# MCU.net
KiCad netlist of a schematic drawn in Altium Designer
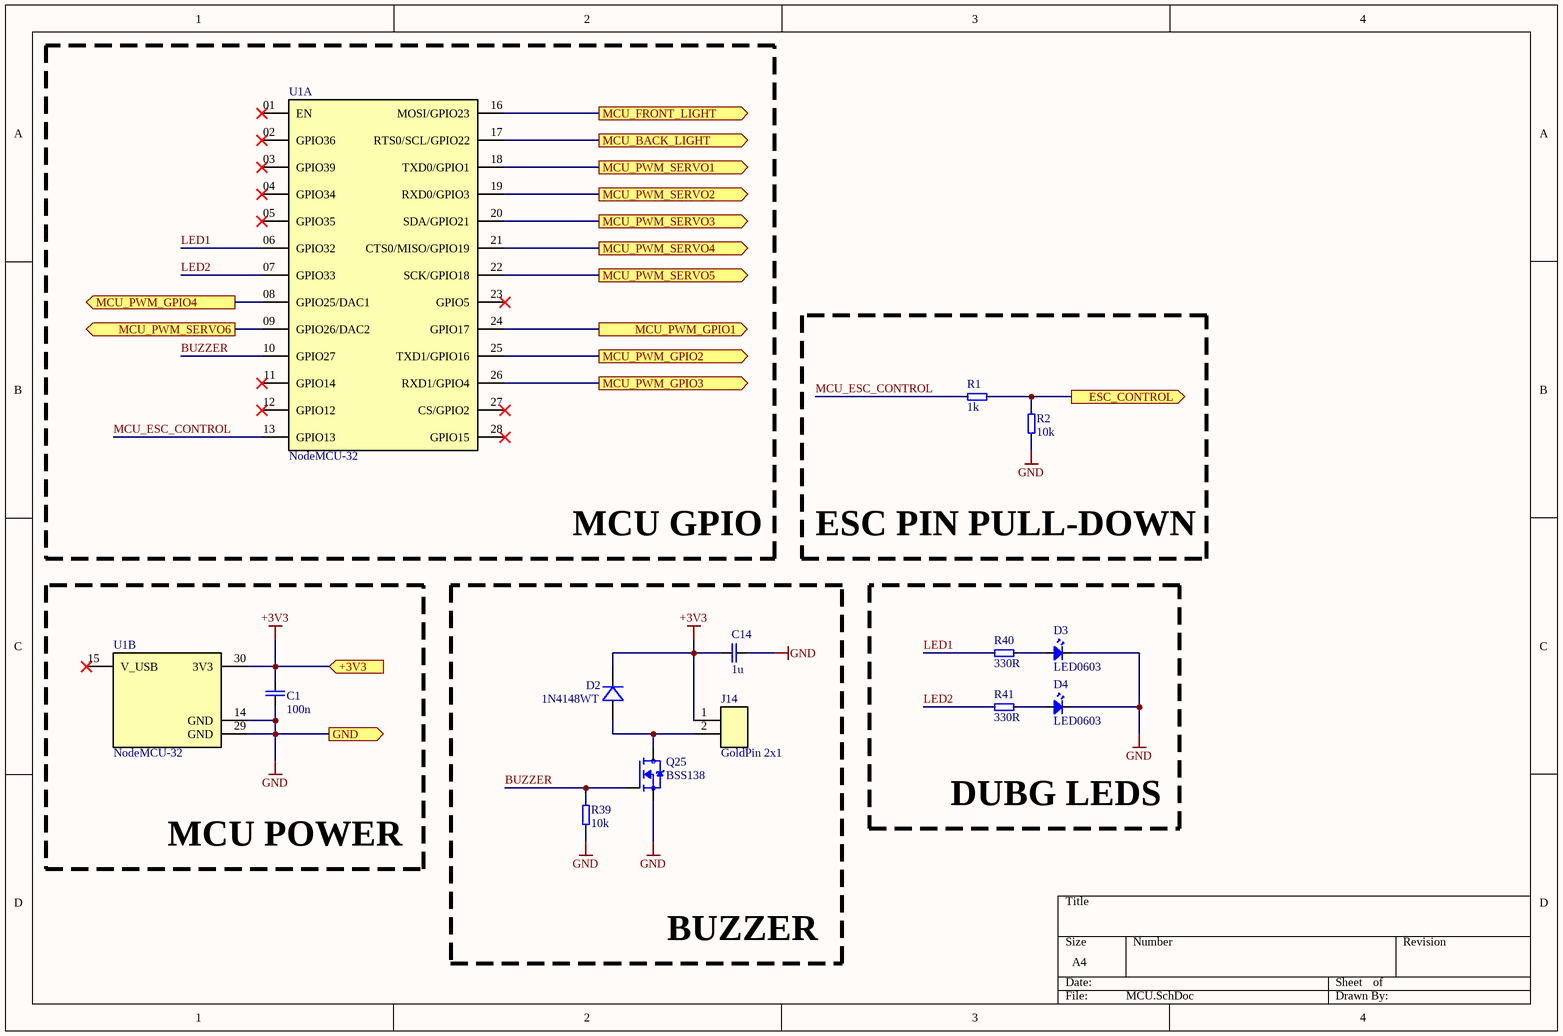
[diagram p0: MCU.SchDoc]

(export (version "E")
  (design (tool "Eeschema 10.0.6"))
  (components
    (comp (ref "C1")
      (value "100n")
      (footprint "C0402")
      (description "Generic SMD 0402 Ceramic Capacitor")
      (libsource (lib "PolSl Racing - Electrical") (part "Capacitor"))
    )
    (comp (ref "C14")
      (value "1u")
      (footprint "C0603")
      (description "Generic 0603 SMD Ceramic Capacitor")
      (libsource (lib "PolSl Racing - Electrical") (part "Capacitor"))
    )
    (comp (ref "D2")
      (value "1N4148WT")
      (footprint "SMBJSeries_LTF")
      (description "Description")
      (fields
        (field (name "MANUFACTURER_PART_NUMBER") "SMBJ7.0A")
        (field (name "COPYRIGHT") "Copyright (C) 2025 Ultra Librarian. All rights reserved.")
      )
      (libsource (lib "Tractor2000") (part "1N4148WT"))
    )
    (comp (ref "D3")
      (value "LED0603")
      (footprint "LED0603")
      (description "0603 LED")
      (libsource (lib "PolSl Racing - Electrical") (part "LED"))
    )
    (comp (ref "D4")
      (value "LED0603")
      (footprint "LED0603")
      (description "0603 LED")
      (libsource (lib "PolSl Racing - Electrical") (part "LED"))
    )
    (comp (ref "J14")
      (value "GoldPin 2x1")
      (footprint "HARWIN_M20-9990246")
      (description "2.54mm (0.1) Pitch SIL Vertical Throughboard Pin Header, 6.1mm mating pin height, tin, 2 contacts")
      (fields (field (name "MF") "Harwin") (field (name "MP") "M20-9990246"))
      (libsource (lib "Tractor2000") (part "GoldPin 2x1"))
    )
    (comp (ref "Q25")
      (value "BSS138")
      (footprint "SOT95P240X111-3N")
      (description "N-Channel 50 V 220mA (Ta) 350mW (Ta) Surface Mount SOT-23-3")
      (fields (field (name "MF") "onsemi"))
      (libsource (lib "Tractor2000") (part "BSS138"))
    )
    (comp (ref "R1")
      (value "1k")
      (footprint "R0402")
      (description "Generic 0402 SMD Resistor")
      (libsource (lib "PolSl Racing - Electrical") (part "Resistor"))
    )
    (comp (ref "R2")
      (value "10k")
      (footprint "R0402")
      (description "Generic 0402 SMD Resistor")
      (libsource (lib "PolSl Racing - Electrical") (part "Resistor"))
    )
    (comp (ref "R39")
      (value "10k")
      (footprint "R0603")
      (description "Generic 0603 SMD Resistor")
      (libsource (lib "PolSl Racing - Electrical") (part "Resistor"))
    )
    (comp (ref "R40")
      (value "330R")
      (footprint "R0603")
      (description "Generic 0603 SMD Resistor")
      (libsource (lib "PolSl Racing - Electrical") (part "Resistor"))
    )
    (comp (ref "R41")
      (value "330R")
      (footprint "R0603")
      (description "Generic 0603 SMD Resistor")
      (libsource (lib "PolSl Racing - Electrical") (part "Resistor"))
    )
    (comp (ref "U1")
      (value "NodeMCU-32")
      (footprint "NodeMCU-32")
      (fields (field (name "MF") "Samtec Inc.") (field (name "MP") "TS-115-T-A"))
      (libsource (lib "Tractor2000") (part "NodeMCU-32"))
    )
  )
  (nets
    (net (code "1") (name "+3V3") (class "Default")
      (node (ref "C1") (pin "2") (pinfunction "2_2") (pintype "passive"))
      (node (ref "C14") (pin "2") (pinfunction "2_2") (pintype "passive"))
      (node (ref "D2") (pin "1") (pinfunction "1_1") (pintype "passive"))
      (node (ref "J14") (pin "1") (pinfunction "1_1") (pintype "passive"))
      (node (ref "U1") (pin "30") (pinfunction "3V3_30") (pintype "passive"))
    )
    (net (code "2") (name "/BUZZER") (class "Default")
      (node (ref "Q25") (pin "1") (pinfunction "G_1") (pintype "passive"))
      (node (ref "R39") (pin "2") (pinfunction "2_2") (pintype "passive"))
      (node (ref "U1") (pin "10") (pinfunction "GPIO27_10") (pintype "passive"))
    )
    (net (code "3") (name "/ESC_CONTROL") (class "Default")
      (node (ref "R1") (pin "2") (pinfunction "2_2") (pintype "passive"))
      (node (ref "R2") (pin "2") (pinfunction "2_2") (pintype "passive"))
    )
    (net (code "4") (name "/LED1") (class "Default")
      (node (ref "R40") (pin "2") (pinfunction "2_2") (pintype "passive"))
      (node (ref "U1") (pin "06") (pinfunction "GPIO32_06") (pintype "passive"))
    )
    (net (code "5") (name "/LED2") (class "Default")
      (node (ref "R41") (pin "2") (pinfunction "2_2") (pintype "passive"))
      (node (ref "U1") (pin "07") (pinfunction "GPIO33_07") (pintype "passive"))
    )
    (net (code "6") (name "/MCU_BACK_LIGHT") (class "Default")
      (node (ref "U1") (pin "17") (pinfunction "RTS0/SCL/GPIO22_17") (pintype "passive"))
    )
    (net (code "7") (name "/MCU_ESC_CONTROL") (class "Default")
      (node (ref "R1") (pin "1") (pinfunction "1_1") (pintype "passive"))
      (node (ref "U1") (pin "13") (pinfunction "GPIO13_13") (pintype "passive"))
    )
    (net (code "8") (name "/MCU_FRONT_LIGHT") (class "Default")
      (node (ref "U1") (pin "16") (pinfunction "MOSI/GPIO23_16") (pintype "passive"))
    )
    (net (code "9") (name "/MCU_PWM_GPIO1") (class "Default")
      (node (ref "U1") (pin "24") (pinfunction "GPIO17_24") (pintype "passive"))
    )
    (net (code "10") (name "/MCU_PWM_GPIO2") (class "Default")
      (node (ref "U1") (pin "25") (pinfunction "TXD1/GPIO16_25") (pintype "passive"))
    )
    (net (code "11") (name "/MCU_PWM_GPIO3") (class "Default")
      (node (ref "U1") (pin "26") (pinfunction "RXD1/GPIO4_26") (pintype "passive"))
    )
    (net (code "12") (name "/MCU_PWM_GPIO4") (class "Default")
      (node (ref "U1") (pin "08") (pinfunction "GPIO25/DAC1_08") (pintype "passive"))
    )
    (net (code "13") (name "/MCU_PWM_SERVO1") (class "Default")
      (node (ref "U1") (pin "18") (pinfunction "TXD0/GPIO1_18") (pintype "passive"))
    )
    (net (code "14") (name "/MCU_PWM_SERVO2") (class "Default")
      (node (ref "U1") (pin "19") (pinfunction "RXD0/GPIO3_19") (pintype "passive"))
    )
    (net (code "15") (name "/MCU_PWM_SERVO3") (class "Default")
      (node (ref "U1") (pin "20") (pinfunction "SDA/GPIO21_20") (pintype "passive"))
    )
    (net (code "16") (name "/MCU_PWM_SERVO4") (class "Default")
      (node (ref "U1") (pin "21") (pinfunction "CTS0/MISO/GPIO19_21") (pintype "passive"))
    )
    (net (code "17") (name "/MCU_PWM_SERVO5") (class "Default")
      (node (ref "U1") (pin "22") (pinfunction "SCK/GPIO18_22") (pintype "passive"))
    )
    (net (code "18") (name "/MCU_PWM_SERVO6") (class "Default")
      (node (ref "U1") (pin "09") (pinfunction "GPIO26/DAC2_09") (pintype "passive"))
    )
    (net (code "19") (name "GND") (class "Default")
      (node (ref "C1") (pin "1") (pinfunction "1_1") (pintype "passive"))
      (node (ref "C14") (pin "1") (pinfunction "1_1") (pintype "passive"))
      (node (ref "D3") (pin "K") (pinfunction "K_K") (pintype "passive"))
      (node (ref "D4") (pin "K") (pinfunction "K_K") (pintype "passive"))
      (node (ref "Q25") (pin "2") (pinfunction "S_2") (pintype "passive"))
      (node (ref "R2") (pin "1") (pinfunction "1_1") (pintype "passive"))
      (node (ref "R39") (pin "1") (pinfunction "1_1") (pintype "passive"))
      (node (ref "U1") (pin "14") (pinfunction "GND_14") (pintype "passive"))
      (node (ref "U1") (pin "29") (pinfunction "GND_29") (pintype "passive"))
    )
    (net (code "20") (name "Net-(D3-PadA)") (class "Default")
      (node (ref "D3") (pin "A") (pinfunction "A_A") (pintype "passive"))
      (node (ref "R40") (pin "1") (pinfunction "1_1") (pintype "passive"))
    )
    (net (code "21") (name "Net-(D4-PadA)") (class "Default")
      (node (ref "D4") (pin "A") (pinfunction "A_A") (pintype "passive"))
      (node (ref "R41") (pin "1") (pinfunction "1_1") (pintype "passive"))
    )
    (net (code "22") (name "Net-(Q25-D)") (class "Default")
      (node (ref "D2") (pin "2") (pinfunction "2_2") (pintype "passive"))
      (node (ref "J14") (pin "2") (pinfunction "2_2") (pintype "passive"))
      (node (ref "Q25") (pin "3") (pinfunction "D_3") (pintype "passive"))
    )
    (net (code "23") (name "unconnected-(U1A-CS{slash}GPIO2-Pad27)") (class "Default")
      (node (ref "U1") (pin "27") (pinfunction "CS/GPIO2_27") (pintype "passive+no_connect"))
    )
    (net (code "24") (name "unconnected-(U1A-EN-Pad01)") (class "Default")
      (node (ref "U1") (pin "01") (pinfunction "EN_01") (pintype "passive+no_connect"))
    )
    (net (code "25") (name "unconnected-(U1A-GPIO5-Pad23)") (class "Default")
      (node (ref "U1") (pin "23") (pinfunction "GPIO5_23") (pintype "passive+no_connect"))
    )
    (net (code "26") (name "unconnected-(U1A-GPIO12-Pad12)") (class "Default")
      (node (ref "U1") (pin "12") (pinfunction "GPIO12_12") (pintype "passive+no_connect"))
    )
    (net (code "27") (name "unconnected-(U1A-GPIO14-Pad11)") (class "Default")
      (node (ref "U1") (pin "11") (pinfunction "GPIO14_11") (pintype "passive+no_connect"))
    )
    (net (code "28") (name "unconnected-(U1A-GPIO15-Pad28)") (class "Default")
      (node (ref "U1") (pin "28") (pinfunction "GPIO15_28") (pintype "passive+no_connect"))
    )
    (net (code "29") (name "unconnected-(U1A-GPIO34-Pad04)") (class "Default")
      (node (ref "U1") (pin "04") (pinfunction "GPIO34_04") (pintype "passive+no_connect"))
    )
    (net (code "30") (name "unconnected-(U1A-GPIO35-Pad05)") (class "Default")
      (node (ref "U1") (pin "05") (pinfunction "GPIO35_05") (pintype "passive+no_connect"))
    )
    (net (code "31") (name "unconnected-(U1A-GPIO36-Pad02)") (class "Default")
      (node (ref "U1") (pin "02") (pinfunction "GPIO36_02") (pintype "passive+no_connect"))
    )
    (net (code "32") (name "unconnected-(U1A-GPIO39-Pad03)") (class "Default")
      (node (ref "U1") (pin "03") (pinfunction "GPIO39_03") (pintype "passive+no_connect"))
    )
    (net (code "33") (name "unconnected-(U1B-V_USB-Pad15)") (class "Default")
      (node (ref "U1") (pin "15") (pinfunction "V_USB_15") (pintype "passive+no_connect"))
    )
  )
)
